# Sheet3.net
KiCad netlist of a schematic drawn in Altium Designer
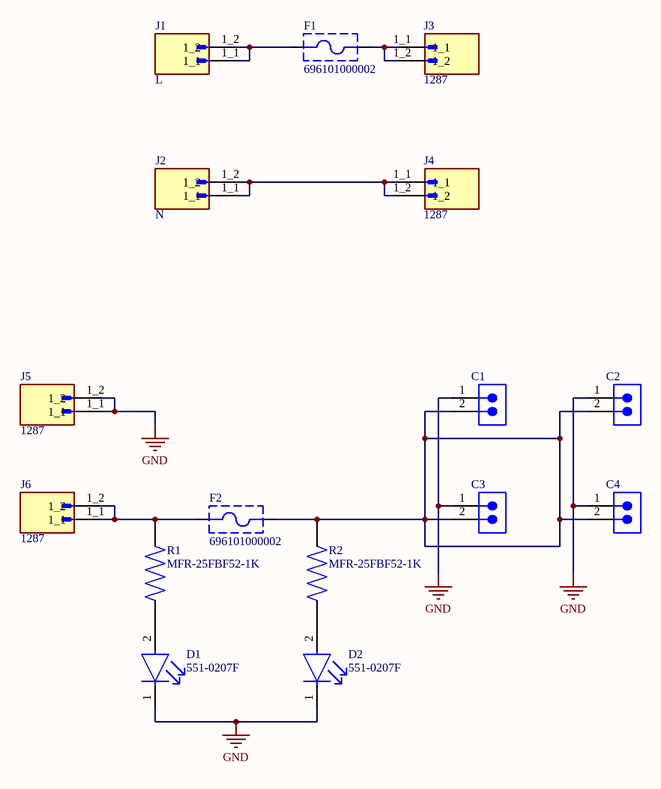
[diagram p0: Sheet3.SchDoc]

(export (version "E")
  (design (tool "Eeschema 10.0.6"))
  (components
    (comp (ref "C1")
      (value "691313510002")
      (footprint "691313510002")
      (description "313; 5.08MM Pitch Straight Pluggable Term Block, Pcb Header, Through Hole, 2 Way")
      (fields (field (name "VOLTAGE") "300V"))
      (libsource (lib "power terminal") (part "CMP-1502-02192-3"))
    )
    (comp (ref "C2")
      (value "691313510002")
      (footprint "691313510002")
      (description "313; 5.08MM Pitch Straight Pluggable Term Block, Pcb Header, Through Hole, 2 Way")
      (fields (field (name "VOLTAGE") "300V"))
      (libsource (lib "power terminal") (part "CMP-1502-02192-3"))
    )
    (comp (ref "C3")
      (value "691313510002")
      (footprint "691313510002")
      (description "313; 5.08MM Pitch Straight Pluggable Term Block, Pcb Header, Through Hole, 2 Way")
      (fields (field (name "VOLTAGE") "300V"))
      (libsource (lib "power terminal") (part "CMP-1502-02192-3"))
    )
    (comp (ref "C4")
      (value "691313510002")
      (footprint "691313510002")
      (description "313; 5.08MM Pitch Straight Pluggable Term Block, Pcb Header, Through Hole, 2 Way")
      (fields (field (name "VOLTAGE") "300V"))
      (libsource (lib "power terminal") (part "CMP-1502-02192-3"))
    )
    (comp (ref "D1")
      (value "551-0207F")
      (footprint "FP-551-0207F-MFG")
      (description "LED 3MM HIGH EFF GREEN")
      (libsource (lib "Right angal 3mm led") (part "CMP-15384-000011-1"))
    )
    (comp (ref "D2")
      (value "551-0207F")
      (footprint "FP-551-0207F-MFG")
      (description "LED 3MM HIGH EFF GREEN")
      (libsource (lib "Right angal 3mm led") (part "CMP-15384-000011-1"))
    )
    (comp (ref "F1")
      (value "696101000002")
      (footprint "696101000002")
      (description "WR-FSH Fuse Holder Blocks Fuse Holder Blocks Clip Cover for PCB")
      (libsource (lib "250v fuse") (part "CMP-1502-00233-4"))
    )
    (comp (ref "F2")
      (value "696101000002")
      (footprint "696101000002")
      (description "WR-FSH Fuse Holder Blocks Fuse Holder Blocks Clip Cover for PCB")
      (libsource (lib "250v fuse") (part "CMP-1502-00233-4"))
    )
    (comp (ref "J1")
      (value "L")
      (footprint "KEYSTONE_1287")
      (description "Male .250 Quick Fit Terminal")
      (fields (field (name "MF") "Keystone Electronics Corp.") (field (name "MP") "1287"))
      (libsource (lib "1287") (part "1287"))
    )
    (comp (ref "J2")
      (value "N")
      (footprint "KEYSTONE_1287")
      (description "Male .250 Quick Fit Terminal")
      (fields (field (name "MF") "Keystone Electronics Corp.") (field (name "MP") "1287"))
      (libsource (lib "1287") (part "1287"))
    )
    (comp (ref "J3")
      (value "1287")
      (footprint "KEYSTONE_1287")
      (description "Male .250 Quick Fit Terminal")
      (fields (field (name "MF") "Keystone Electronics Corp."))
      (libsource (lib "") (part "1287_1"))
    )
    (comp (ref "J4")
      (value "1287")
      (footprint "KEYSTONE_1287")
      (description "Male .250 Quick Fit Terminal")
      (fields (field (name "MF") "Keystone Electronics Corp."))
      (libsource (lib "") (part "1287_1"))
    )
    (comp (ref "J5")
      (value "1287")
      (footprint "KEYSTONE_1287")
      (description "Male .250 Quick Fit Terminal")
      (fields (field (name "MF") "Keystone Electronics Corp."))
      (libsource (lib "1287") (part "1287"))
    )
    (comp (ref "J6")
      (value "1287")
      (footprint "KEYSTONE_1287")
      (description "Male .250 Quick Fit Terminal")
      (fields (field (name "MF") "Keystone Electronics Corp."))
      (libsource (lib "1287") (part "1287"))
    )
    (comp (ref "R1")
      (value "MFR-25FBF52-1K")
      (footprint "RESAD1100W55L680D260")
      (description "1.07 kOhms Â±1% 0.25W, 1/4W Through Hole Resistor Axial - Metal Film")
      (fields (field (name "MF") "Yageo"))
      (libsource (lib "MFR-25FBF52-1K (1)") (part "MFR-25FBF52-1K"))
    )
    (comp (ref "R2")
      (value "MFR-25FBF52-1K")
      (footprint "RESAD1100W55L680D260")
      (description "1.07 kOhms Â±1% 0.25W, 1/4W Through Hole Resistor Axial - Metal Film")
      (fields (field (name "MF") "Yageo"))
      (libsource (lib "MFR-25FBF52-1K (1)") (part "MFR-25FBF52-1K"))
    )
  )
  (nets
    (net (code "1") (name "GND") (class "Default")
      (node (ref "C1") (pin "1") (pinfunction "1_1") (pintype "passive"))
      (node (ref "C2") (pin "1") (pinfunction "1_1") (pintype "passive"))
      (node (ref "C3") (pin "1") (pinfunction "1_1") (pintype "passive"))
      (node (ref "C4") (pin "1") (pinfunction "1_1") (pintype "passive"))
      (node (ref "D1") (pin "1") (pinfunction "C_1") (pintype "passive"))
      (node (ref "D2") (pin "1") (pinfunction "C_1") (pintype "passive"))
      (node (ref "J5") (pin "1_1") (pinfunction "1_1_1_1") (pintype "passive"))
      (node (ref "J5") (pin "1_2") (pinfunction "1_2_1_2") (pintype "passive"))
    )
    (net (code "2") (name "Net-(C1-Pad2)") (class "Default")
      (node (ref "C1") (pin "2") (pinfunction "2_2") (pintype "passive"))
      (node (ref "C2") (pin "2") (pinfunction "2_2") (pintype "passive"))
      (node (ref "C3") (pin "2") (pinfunction "2_2") (pintype "passive"))
      (node (ref "C4") (pin "2") (pinfunction "2_2") (pintype "passive"))
      (node (ref "F2") (pin "2") (pinfunction "2_2") (pintype "passive"))
      (node (ref "R2") (pin "2") (pinfunction "2_2") (pintype "passive"))
    )
    (net (code "3") (name "Net-(D1-A)") (class "Default")
      (node (ref "D1") (pin "2") (pinfunction "A_2") (pintype "passive"))
      (node (ref "R1") (pin "1") (pinfunction "1_1") (pintype "passive"))
    )
    (net (code "4") (name "Net-(D2-A)") (class "Default")
      (node (ref "D2") (pin "2") (pinfunction "A_2") (pintype "passive"))
      (node (ref "R2") (pin "1") (pinfunction "1_1") (pintype "passive"))
    )
    (net (code "5") (name "Net-(F1-Pad1)") (class "Default")
      (node (ref "F1") (pin "1") (pinfunction "1_1") (pintype "passive"))
      (node (ref "J1") (pin "1_1") (pinfunction "1_1_1_1") (pintype "passive"))
      (node (ref "J1") (pin "1_2") (pinfunction "1_2_1_2") (pintype "passive"))
    )
    (net (code "6") (name "Net-(F1-Pad2)") (class "Default")
      (node (ref "F1") (pin "2") (pinfunction "2_2") (pintype "passive"))
      (node (ref "J3") (pin "1_1") (pinfunction "1_1_1_1") (pintype "passive"))
      (node (ref "J3") (pin "1_2") (pinfunction "1_2_1_2") (pintype "passive"))
    )
    (net (code "7") (name "Net-(F2-Pad1)") (class "Default")
      (node (ref "F2") (pin "1") (pinfunction "1_1") (pintype "passive"))
      (node (ref "J6") (pin "1_1") (pinfunction "1_1_1_1") (pintype "passive"))
      (node (ref "J6") (pin "1_2") (pinfunction "1_2_1_2") (pintype "passive"))
      (node (ref "R1") (pin "2") (pinfunction "2_2") (pintype "passive"))
    )
    (net (code "8") (name "Net-(J2-Pad1_1)") (class "Default")
      (node (ref "J2") (pin "1_1") (pinfunction "1_1_1_1") (pintype "passive"))
      (node (ref "J2") (pin "1_2") (pinfunction "1_2_1_2") (pintype "passive"))
      (node (ref "J4") (pin "1_1") (pinfunction "1_1_1_1") (pintype "passive"))
      (node (ref "J4") (pin "1_2") (pinfunction "1_2_1_2") (pintype "passive"))
    )
  )
)
